# PIC_16F877A_Board_V4.net
KiCad netlist of a schematic drawn in EAGLE
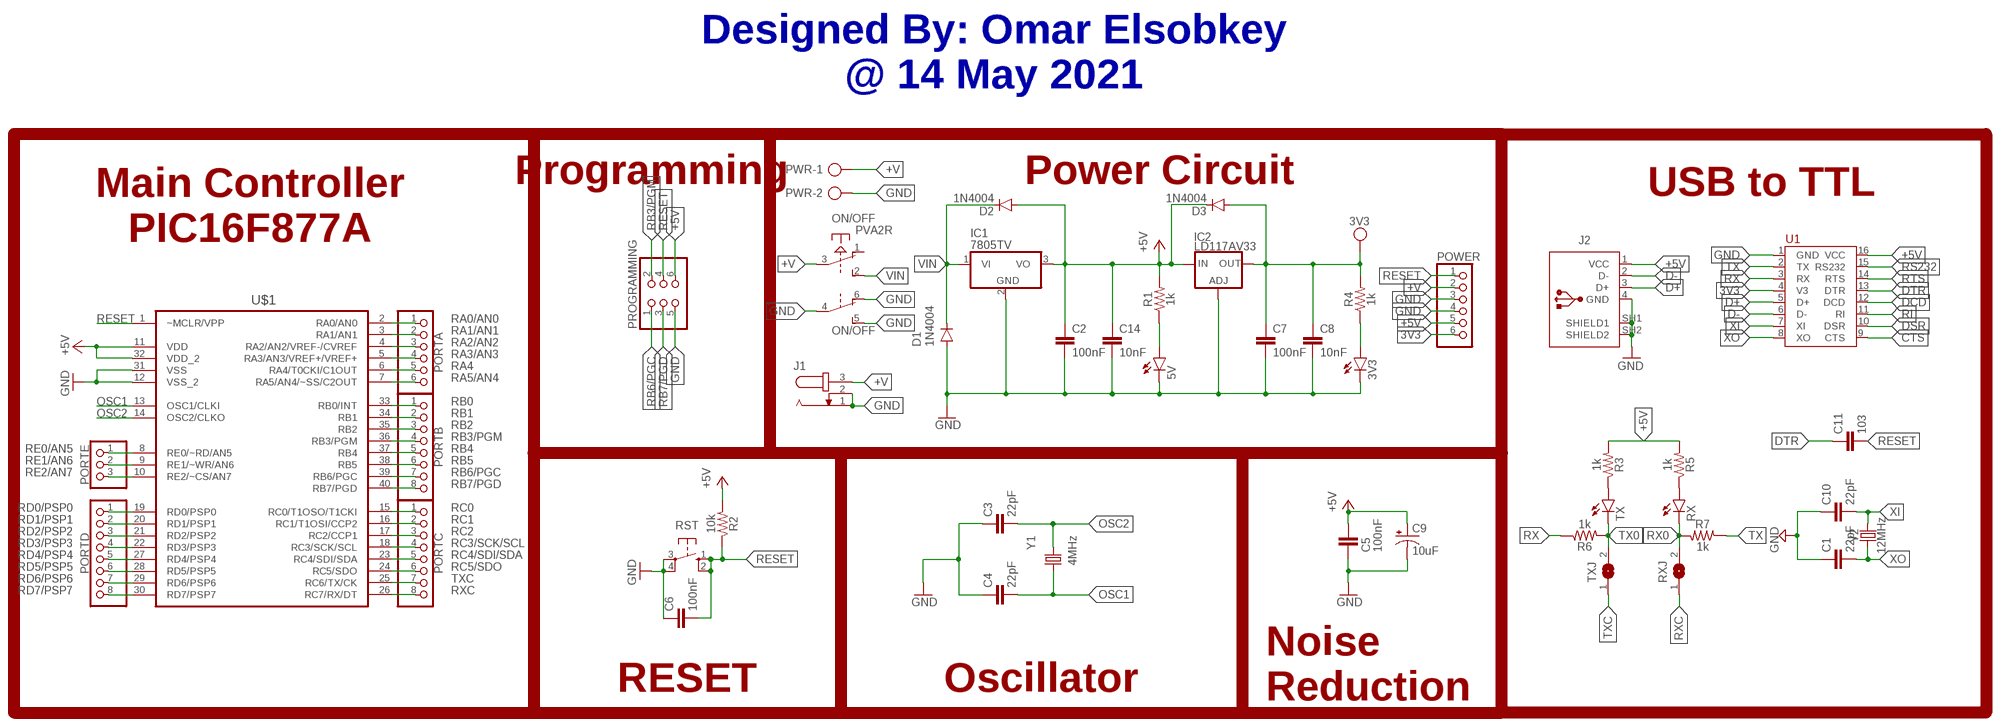
[diagram p0: schematic, sheet 1]

(export (version "E")
  (design (tool "Eeschema 10.0.6"))
  (components
    (comp (ref "3V3")
      (value "LED3MM")
      (footprint "eagle-import:LED3MM")
      (libsource (lib "eagle-import") (part "LED3MM"))
    )
    (comp (ref "5V")
      (value "LED3MM")
      (footprint "eagle-import:LED3MM")
      (libsource (lib "eagle-import") (part "LED3MM"))
    )
    (comp (ref "C1")
      (value "22pF")
      (footprint "eagle-import:C025-025X050")
      (libsource (lib "eagle-import") (part "C-EU025-025X050"))
    )
    (comp (ref "C2")
      (value "100nF")
      (footprint "eagle-import:C025-025X050")
      (libsource (lib "eagle-import") (part "C-EU025-025X050"))
    )
    (comp (ref "C3")
      (value "22pF")
      (footprint "eagle-import:C025-025X050")
      (libsource (lib "eagle-import") (part "C-EU025-025X050"))
    )
    (comp (ref "C4")
      (value "22pF")
      (footprint "eagle-import:C025-025X050")
      (libsource (lib "eagle-import") (part "C-EU025-025X050"))
    )
    (comp (ref "C5")
      (value "100nF")
      (footprint "eagle-import:C025-025X050")
      (libsource (lib "eagle-import") (part "C-EU025-025X050"))
    )
    (comp (ref "C6")
      (value "100nF")
      (footprint "eagle-import:C025-025X050")
      (libsource (lib "eagle-import") (part "C-EU025-025X050"))
    )
    (comp (ref "C7")
      (value "100nF")
      (footprint "eagle-import:C025-025X050")
      (libsource (lib "eagle-import") (part "C-EU025-025X050"))
    )
    (comp (ref "C8")
      (value "10nF")
      (footprint "eagle-import:C025-025X050")
      (libsource (lib "eagle-import") (part "C-EU025-025X050"))
    )
    (comp (ref "C9")
      (value "10uF")
      (footprint "eagle-import:CPOL-RADIAL-2.5MM-5MM-KIT")
      (libsource (lib "eagle-import") (part "10UF-POLAR-RADIAL-2.5MM-KIT-25V-20%"))
    )
    (comp (ref "C10")
      (value "22pF")
      (footprint "eagle-import:C025-025X050")
      (libsource (lib "eagle-import") (part "C-EU025-025X050"))
    )
    (comp (ref "C11")
      (value "103")
      (footprint "eagle-import:C025-025X050")
      (libsource (lib "eagle-import") (part "C-EU025-025X050"))
    )
    (comp (ref "C14")
      (value "10nF")
      (footprint "eagle-import:C025-025X050")
      (libsource (lib "eagle-import") (part "C-EU025-025X050"))
    )
    (comp (ref "D1")
      (value "1N4004")
      (footprint "eagle-import:DO41-10")
      (libsource (lib "eagle-import") (part "1N4004"))
    )
    (comp (ref "D2")
      (value "1N4004")
      (footprint "eagle-import:DO41-10")
      (libsource (lib "eagle-import") (part "1N4004"))
    )
    (comp (ref "D3")
      (value "1N4004")
      (footprint "eagle-import:DO41-10")
      (libsource (lib "eagle-import") (part "1N4004"))
    )
    (comp (ref "IC1")
      (value "7805TV")
      (footprint "eagle-import:TO220V")
      (libsource (lib "eagle-import") (part "78TV05"))
    )
    (comp (ref "IC2")
      (value "LD117AV33")
      (footprint "eagle-import:TO220L1")
      (libsource (lib "eagle-import") (part "LD117A?V33"))
    )
    (comp (ref "J1")
      (value "JACK-PLUG0")
      (footprint "eagle-import:SPC4077")
      (libsource (lib "eagle-import") (part "JACK-PLUG0"))
    )
    (comp (ref "J2")
      (value "61729-1011")
      (footprint "eagle-import:61729-1011BLF")
      (fields (field (name "MANUFACTURER") "Amphenol ICC (FCI)") (field (name "MPN") "61729-1011BLF"))
      (libsource (lib "eagle-import") (part "61729-1011"))
    )
    (comp (ref "ON/OFF")
      (value "PVA2R")
      (footprint "eagle-import:PVA2R")
      (libsource (lib "eagle-import") (part "PVA2R"))
    )
    (comp (ref "PORTA")
      (value "PINHD-1X6")
      (footprint "eagle-import:1X06")
      (libsource (lib "eagle-import") (part "PINHD-1X6"))
    )
    (comp (ref "PORTB")
      (value "PINHD-1X8")
      (footprint "eagle-import:1X08")
      (libsource (lib "eagle-import") (part "PINHD-1X8"))
    )
    (comp (ref "PORTC")
      (value "PINHD-1X8")
      (footprint "eagle-import:1X08")
      (libsource (lib "eagle-import") (part "PINHD-1X8"))
    )
    (comp (ref "PORTD")
      (value "PINHD-1X8")
      (footprint "eagle-import:1X08")
      (libsource (lib "eagle-import") (part "PINHD-1X8"))
    )
    (comp (ref "PORTE")
      (value "PINHD-1X3")
      (footprint "eagle-import:1X03")
      (libsource (lib "eagle-import") (part "PINHD-1X3"))
    )
    (comp (ref "POWER")
      (value "PINHD-1X6")
      (footprint "eagle-import:1X06")
      (libsource (lib "eagle-import") (part "PINHD-1X6"))
    )
    (comp (ref "PROGRAMMING")
      (value "PINHD-2X3")
      (footprint "eagle-import:2X03")
      (libsource (lib "eagle-import") (part "PINHD-2X3"))
    )
    (comp (ref "PWR")
      (value "AK500/2-H")
      (footprint "eagle-import:AK500_2-H")
      (libsource (lib "eagle-import") (part "AK500/2-H"))
    )
    (comp (ref "R1")
      (value "1k")
      (footprint "eagle-import:1206")
      (libsource (lib "eagle-import") (part "RESISTOR1206"))
    )
    (comp (ref "R2")
      (value "10k")
      (footprint "eagle-import:1206")
      (libsource (lib "eagle-import") (part "RESISTOR1206"))
    )
    (comp (ref "R3")
      (value "1k")
      (footprint "eagle-import:1206")
      (libsource (lib "eagle-import") (part "RESISTOR1206"))
    )
    (comp (ref "R4")
      (value "1k")
      (footprint "eagle-import:1206")
      (libsource (lib "eagle-import") (part "RESISTOR1206"))
    )
    (comp (ref "R5")
      (value "1k")
      (footprint "eagle-import:1206")
      (libsource (lib "eagle-import") (part "RESISTOR1206"))
    )
    (comp (ref "R6")
      (value "1k")
      (footprint "eagle-import:1206")
      (libsource (lib "eagle-import") (part "RESISTOR1206"))
    )
    (comp (ref "R7")
      (value "1k")
      (footprint "eagle-import:1206")
      (libsource (lib "eagle-import") (part "RESISTOR1206"))
    )
    (comp (ref "RST")
      (value "10-XX")
      (footprint "eagle-import:B3F-10XX")
      (fields (field (name "MPN") "B3F-1000"))
      (libsource (lib "eagle-import") (part "10-XX"))
    )
    (comp (ref "RX")
      (value "LED3MM")
      (footprint "eagle-import:LED3MM")
      (libsource (lib "eagle-import") (part "LED3MM"))
    )
    (comp (ref "RXJ")
      (value "SJW")
      (footprint "eagle-import:SJW")
      (libsource (lib "eagle-import") (part "SJW"))
    )
    (comp (ref "TX")
      (value "LED3MM")
      (footprint "eagle-import:LED3MM")
      (libsource (lib "eagle-import") (part "LED3MM"))
    )
    (comp (ref "TXJ")
      (value "SJW")
      (footprint "eagle-import:SJW")
      (libsource (lib "eagle-import") (part "SJW"))
    )
    (comp (ref "U$1")
      (value "PIC16F877A-I/P")
      (footprint "eagle-import:PDIP-40")
      (fields (field (name "MF") "Microchip"))
      (libsource (lib "eagle-import") (part "PIC16F877A-I/P"))
    )
    (comp (ref "U1")
      (value "CH340G")
      (footprint "eagle-import:SOP-16")
      (libsource (lib "eagle-import") (part "CH340G"))
    )
    (comp (ref "Y1")
      (value "4MHz")
      (footprint "eagle-import:HC49U")
      (libsource (lib "eagle-import") (part "CRYSTALPTH-HC49UV"))
    )
    (comp (ref "Y2")
      (value "12MHz")
      (footprint "eagle-import:HC49U")
      (libsource (lib "eagle-import") (part "CRYSTALPTH-HC49UV"))
    )
  )
  (nets
    (net (code "1") (name "+5V") (class "Default")
      (node (ref "C14") (pin "1") (pinfunction "1_1") (pintype "passive"))
      (node (ref "C2") (pin "1") (pinfunction "1_1") (pintype "passive"))
      (node (ref "C5") (pin "2") (pinfunction "2_2") (pintype "passive"))
      (node (ref "C9") (pin "1") (pinfunction "+_1") (pintype "passive"))
      (node (ref "D2") (pin "A") (pinfunction "A_A") (pintype "passive"))
      (node (ref "D3") (pin "C") (pinfunction "C_C") (pintype "passive"))
      (node (ref "IC1") (pin "3") (pinfunction "VO_3") (pintype "passive"))
      (node (ref "IC2") (pin "3") (pinfunction "IN_3") (pintype "input"))
      (node (ref "J2") (pin "1") (pinfunction "VCC_1") (pintype "power_in"))
      (node (ref "POWER") (pin "5") (pinfunction "5_5") (pintype "passive"))
      (node (ref "PROGRAMMING") (pin "6") (pinfunction "6_6") (pintype "passive"))
      (node (ref "R1") (pin "2") (pinfunction "2_2") (pintype "passive"))
      (node (ref "R2") (pin "2") (pinfunction "2_2") (pintype "passive"))
      (node (ref "R3") (pin "2") (pinfunction "2_2") (pintype "passive"))
      (node (ref "R5") (pin "2") (pinfunction "2_2") (pintype "passive"))
      (node (ref "U$1") (pin "11") (pinfunction "VDD_11") (pintype "power_in"))
      (node (ref "U$1") (pin "32") (pinfunction "VDD_2_32") (pintype "power_in"))
      (node (ref "U1") (pin "16") (pinfunction "VCC_16") (pintype "bidirectional"))
    )
    (net (code "2") (name "+V") (class "Default")
      (node (ref "J1") (pin "3") (pinfunction "3_3") (pintype "passive"))
      (node (ref "ON/OFF") (pin "3") (pinfunction "P_3") (pintype "passive"))
      (node (ref "POWER") (pin "2") (pinfunction "2_2") (pintype "passive"))
      (node (ref "PWR") (pin "1") (pinfunction "KL_1") (pintype "passive"))
    )
    (net (code "3") (name "/RA0{slash}AN0") (class "Default")
      (node (ref "PORTA") (pin "1") (pinfunction "1_1") (pintype "passive"))
      (node (ref "U$1") (pin "2") (pinfunction "RA0/AN0_2") (pintype "bidirectional"))
    )
    (net (code "4") (name "/RA1{slash}AN1") (class "Default")
      (node (ref "PORTA") (pin "2") (pinfunction "2_2") (pintype "passive"))
      (node (ref "U$1") (pin "3") (pinfunction "RA1/AN1_3") (pintype "bidirectional"))
    )
    (net (code "5") (name "/RA2{slash}AN2") (class "Default")
      (node (ref "PORTA") (pin "3") (pinfunction "3_3") (pintype "passive"))
      (node (ref "U$1") (pin "4") (pinfunction "RA2/AN2/VREF-/CVREF_4") (pintype "bidirectional"))
    )
    (net (code "6") (name "/RA3{slash}AN3") (class "Default")
      (node (ref "PORTA") (pin "4") (pinfunction "4_4") (pintype "passive"))
      (node (ref "U$1") (pin "5") (pinfunction "RA3/AN3/VREF+/VREF+_5") (pintype "bidirectional"))
    )
    (net (code "7") (name "/RA4") (class "Default")
      (node (ref "PORTA") (pin "5") (pinfunction "5_5") (pintype "passive"))
      (node (ref "U$1") (pin "6") (pinfunction "RA4/T0CKI/C1OUT_6") (pintype "bidirectional"))
    )
    (net (code "8") (name "/RA5{slash}AN4") (class "Default")
      (node (ref "PORTA") (pin "6") (pinfunction "6_6") (pintype "passive"))
      (node (ref "U$1") (pin "7") (pinfunction "RA5/AN4/~{SS/C2OUT}_7") (pintype "bidirectional"))
    )
    (net (code "9") (name "/RB0") (class "Default")
      (node (ref "PORTB") (pin "1") (pinfunction "1_1") (pintype "passive"))
      (node (ref "U$1") (pin "33") (pinfunction "RB0/INT_33") (pintype "bidirectional"))
    )
    (net (code "10") (name "/RB1") (class "Default")
      (node (ref "PORTB") (pin "2") (pinfunction "2_2") (pintype "passive"))
      (node (ref "U$1") (pin "34") (pinfunction "RB1_34") (pintype "bidirectional"))
    )
    (net (code "11") (name "/RB2") (class "Default")
      (node (ref "PORTB") (pin "3") (pinfunction "3_3") (pintype "passive"))
      (node (ref "U$1") (pin "35") (pinfunction "RB2_35") (pintype "bidirectional"))
    )
    (net (code "12") (name "/RB4") (class "Default")
      (node (ref "PORTB") (pin "5") (pinfunction "5_5") (pintype "passive"))
      (node (ref "U$1") (pin "37") (pinfunction "RB4_37") (pintype "bidirectional"))
    )
    (net (code "13") (name "/RB5") (class "Default")
      (node (ref "PORTB") (pin "6") (pinfunction "6_6") (pintype "passive"))
      (node (ref "U$1") (pin "38") (pinfunction "RB5_38") (pintype "bidirectional"))
    )
    (net (code "14") (name "/RC0") (class "Default")
      (node (ref "PORTC") (pin "1") (pinfunction "1_1") (pintype "passive"))
      (node (ref "U$1") (pin "15") (pinfunction "RC0/T1OSO/T1CKI_15") (pintype "bidirectional"))
    )
    (net (code "15") (name "/RC1") (class "Default")
      (node (ref "PORTC") (pin "2") (pinfunction "2_2") (pintype "passive"))
      (node (ref "U$1") (pin "16") (pinfunction "RC1/T1OSI/CCP2_16") (pintype "bidirectional"))
    )
    (net (code "16") (name "/RC2") (class "Default")
      (node (ref "PORTC") (pin "3") (pinfunction "3_3") (pintype "passive"))
      (node (ref "U$1") (pin "17") (pinfunction "RC2/CCP1_17") (pintype "bidirectional"))
    )
    (net (code "17") (name "/RC3{slash}SCK{slash}SCL") (class "Default")
      (node (ref "PORTC") (pin "4") (pinfunction "4_4") (pintype "passive"))
      (node (ref "U$1") (pin "18") (pinfunction "RC3/SCK/SCL_18") (pintype "bidirectional"))
    )
    (net (code "18") (name "/RC4{slash}SDI{slash}SDA") (class "Default")
      (node (ref "PORTC") (pin "5") (pinfunction "5_5") (pintype "passive"))
      (node (ref "U$1") (pin "23") (pinfunction "RC4/SDI/SDA_23") (pintype "bidirectional"))
    )
    (net (code "19") (name "/RC5{slash}SDO") (class "Default")
      (node (ref "PORTC") (pin "6") (pinfunction "6_6") (pintype "passive"))
      (node (ref "U$1") (pin "24") (pinfunction "RC5/SDO_24") (pintype "bidirectional"))
    )
    (net (code "20") (name "/RD0{slash}PSP0") (class "Default")
      (node (ref "PORTD") (pin "1") (pinfunction "1_1") (pintype "passive"))
      (node (ref "U$1") (pin "19") (pinfunction "RD0/PSP0_19") (pintype "bidirectional"))
    )
    (net (code "21") (name "/RD1{slash}PSP1") (class "Default")
      (node (ref "PORTD") (pin "2") (pinfunction "2_2") (pintype "passive"))
      (node (ref "U$1") (pin "20") (pinfunction "RD1/PSP1_20") (pintype "bidirectional"))
    )
    (net (code "22") (name "/RD2{slash}PSP2") (class "Default")
      (node (ref "PORTD") (pin "3") (pinfunction "3_3") (pintype "passive"))
      (node (ref "U$1") (pin "21") (pinfunction "RD2/PSP2_21") (pintype "bidirectional"))
    )
    (net (code "23") (name "/RD3{slash}PSP3") (class "Default")
      (node (ref "PORTD") (pin "4") (pinfunction "4_4") (pintype "passive"))
      (node (ref "U$1") (pin "22") (pinfunction "RD3/PSP3_22") (pintype "bidirectional"))
    )
    (net (code "24") (name "/RD4{slash}PSP4") (class "Default")
      (node (ref "PORTD") (pin "5") (pinfunction "5_5") (pintype "passive"))
      (node (ref "U$1") (pin "27") (pinfunction "RD4/PSP4_27") (pintype "bidirectional"))
    )
    (net (code "25") (name "/RD5{slash}PSP5") (class "Default")
      (node (ref "PORTD") (pin "6") (pinfunction "6_6") (pintype "passive"))
      (node (ref "U$1") (pin "28") (pinfunction "RD5/PSP5_28") (pintype "bidirectional"))
    )
    (net (code "26") (name "/RD6{slash}PSP6") (class "Default")
      (node (ref "PORTD") (pin "7") (pinfunction "7_7") (pintype "passive"))
      (node (ref "U$1") (pin "29") (pinfunction "RD6/PSP6_29") (pintype "bidirectional"))
    )
    (net (code "27") (name "/RD7{slash}PSP7") (class "Default")
      (node (ref "PORTD") (pin "8") (pinfunction "8_8") (pintype "passive"))
      (node (ref "U$1") (pin "30") (pinfunction "RD7/PSP7_30") (pintype "bidirectional"))
    )
    (net (code "28") (name "/RE0{slash}AN5") (class "Default")
      (node (ref "PORTE") (pin "1") (pinfunction "1_1") (pintype "passive"))
      (node (ref "U$1") (pin "8") (pinfunction "RE0/~{RD/AN5}_8") (pintype "bidirectional"))
    )
    (net (code "29") (name "/RE1{slash}AN6") (class "Default")
      (node (ref "PORTE") (pin "2") (pinfunction "2_2") (pintype "passive"))
      (node (ref "U$1") (pin "9") (pinfunction "RE1/~{WR/AN6}_9") (pintype "bidirectional"))
    )
    (net (code "30") (name "/RE2{slash}AN7") (class "Default")
      (node (ref "PORTE") (pin "3") (pinfunction "3_3") (pintype "passive"))
      (node (ref "U$1") (pin "10") (pinfunction "RE2/~{CS/AN7}_10") (pintype "bidirectional"))
    )
    (net (code "31") (name "3V3") (class "Default")
      (node (ref "C7") (pin "1") (pinfunction "1_1") (pintype "passive"))
      (node (ref "C8") (pin "1") (pinfunction "1_1") (pintype "passive"))
      (node (ref "D3") (pin "A") (pinfunction "A_A") (pintype "passive"))
      (node (ref "IC2") (pin "2") (pinfunction "OUT_2") (pintype "passive"))
      (node (ref "POWER") (pin "6") (pinfunction "6_6") (pintype "passive"))
      (node (ref "R4") (pin "2") (pinfunction "2_2") (pintype "passive"))
      (node (ref "U1") (pin "4") (pinfunction "V3_4") (pintype "bidirectional"))
    )
    (net (code "32") (name "CTS") (class "Default")
      (node (ref "U1") (pin "9") (pinfunction "CTS_9") (pintype "bidirectional"))
    )
    (net (code "33") (name "D+") (class "Default")
      (node (ref "J2") (pin "3") (pinfunction "D+_3") (pintype "bidirectional"))
      (node (ref "U1") (pin "5") (pinfunction "D+_5") (pintype "bidirectional"))
    )
    (net (code "34") (name "D-") (class "Default")
      (node (ref "J2") (pin "2") (pinfunction "D-_2") (pintype "bidirectional"))
      (node (ref "U1") (pin "6") (pinfunction "D-_6") (pintype "bidirectional"))
    )
    (net (code "35") (name "DCD") (class "Default")
      (node (ref "U1") (pin "12") (pinfunction "DCD_12") (pintype "bidirectional"))
    )
    (net (code "36") (name "DSR") (class "Default")
      (node (ref "U1") (pin "10") (pinfunction "DSR_10") (pintype "bidirectional"))
    )
    (net (code "37") (name "DTR") (class "Default")
      (node (ref "C11") (pin "1") (pinfunction "1_1") (pintype "passive"))
      (node (ref "U1") (pin "13") (pinfunction "DTR_13") (pintype "bidirectional"))
    )
    (net (code "38") (name "GND") (class "Default")
      (node (ref "3V3") (pin "K") (pinfunction "C_K") (pintype "passive"))
      (node (ref "5V") (pin "K") (pinfunction "C_K") (pintype "passive"))
      (node (ref "C1") (pin "1") (pinfunction "1_1") (pintype "passive"))
      (node (ref "C10") (pin "1") (pinfunction "1_1") (pintype "passive"))
      (node (ref "C14") (pin "2") (pinfunction "2_2") (pintype "passive"))
      (node (ref "C2") (pin "2") (pinfunction "2_2") (pintype "passive"))
      (node (ref "C3") (pin "1") (pinfunction "1_1") (pintype "passive"))
      (node (ref "C4") (pin "1") (pinfunction "1_1") (pintype "passive"))
      (node (ref "C5") (pin "1") (pinfunction "1_1") (pintype "passive"))
      (node (ref "C6") (pin "1") (pinfunction "1_1") (pintype "passive"))
      (node (ref "C7") (pin "2") (pinfunction "2_2") (pintype "passive"))
      (node (ref "C8") (pin "2") (pinfunction "2_2") (pintype "passive"))
      (node (ref "C9") (pin "2") (pinfunction "-_2") (pintype "passive"))
      (node (ref "D1") (pin "A") (pinfunction "A_A") (pintype "passive"))
      (node (ref "IC1") (pin "2") (pinfunction "GND_2") (pintype "passive"))
      (node (ref "IC2") (pin "1") (pinfunction "ADJ_1") (pintype "input"))
      (node (ref "J1") (pin "1") (pinfunction "1_1") (pintype "passive"))
      (node (ref "J1") (pin "2") (pinfunction "2_2") (pintype "passive"))
      (node (ref "J2") (pin "4") (pinfunction "GND_4") (pintype "power_in"))
      (node (ref "J2") (pin "SH1") (pinfunction "SHIELD1_SH1") (pintype "power_in"))
      (node (ref "J2") (pin "SH2") (pinfunction "SHIELD2_SH2") (pintype "power_in"))
      (node (ref "ON/OFF") (pin "4") (pinfunction "P_4") (pintype "passive"))
      (node (ref "ON/OFF") (pin "5") (pinfunction "S_5") (pintype "passive"))
      (node (ref "ON/OFF") (pin "6") (pinfunction "O_6") (pintype "passive"))
      (node (ref "POWER") (pin "3") (pinfunction "3_3") (pintype "passive"))
      (node (ref "POWER") (pin "4") (pinfunction "4_4") (pintype "passive"))
      (node (ref "PROGRAMMING") (pin "5") (pinfunction "5_5") (pintype "passive"))
      (node (ref "PWR") (pin "2") (pinfunction "KL_2") (pintype "passive"))
      (node (ref "RST") (pin "3") (pinfunction "P_3") (pintype "passive"))
      (node (ref "RST") (pin "4") (pinfunction "P1_4") (pintype "passive"))
      (node (ref "U$1") (pin "12") (pinfunction "VSS_2_12") (pintype "power_in"))
      (node (ref "U$1") (pin "31") (pinfunction "VSS_31") (pintype "power_in"))
      (node (ref "U1") (pin "1") (pinfunction "GND_1") (pintype "bidirectional"))
    )
    (net (code "39") (name "Net-(3V3-PadA)") (class "Default")
      (node (ref "3V3") (pin "A") (pinfunction "A_A") (pintype "passive"))
      (node (ref "R4") (pin "1") (pinfunction "1_1") (pintype "passive"))
    )
    (net (code "40") (name "Net-(5V-PadA)") (class "Default")
      (node (ref "5V") (pin "A") (pinfunction "A_A") (pintype "passive"))
      (node (ref "R1") (pin "1") (pinfunction "1_1") (pintype "passive"))
    )
    (net (code "41") (name "Net-(R3-Pad1)") (class "Default")
      (node (ref "R3") (pin "1") (pinfunction "1_1") (pintype "passive"))
      (node (ref "TX") (pin "A") (pinfunction "A_A") (pintype "passive"))
    )
    (net (code "42") (name "Net-(R5-Pad1)") (class "Default")
      (node (ref "R5") (pin "1") (pinfunction "1_1") (pintype "passive"))
      (node (ref "RX") (pin "A") (pinfunction "A_A") (pintype "passive"))
    )
    (net (code "43") (name "OSC1") (class "Default")
      (node (ref "C4") (pin "2") (pinfunction "2_2") (pintype "passive"))
      (node (ref "U$1") (pin "13") (pinfunction "OSC1/CLKI_13") (pintype "input"))
      (node (ref "Y1") (pin "2") (pinfunction "2_2") (pintype "passive"))
    )
    (net (code "44") (name "OSC2") (class "Default")
      (node (ref "C3") (pin "2") (pinfunction "2_2") (pintype "passive"))
      (node (ref "U$1") (pin "14") (pinfunction "OSC2/CLKO_14") (pintype "output"))
      (node (ref "Y1") (pin "1") (pinfunction "1_1") (pintype "passive"))
    )
    (net (code "45") (name "RB3{slash}PGM") (class "Default")
      (node (ref "PORTB") (pin "4") (pinfunction "4_4") (pintype "passive"))
      (node (ref "PROGRAMMING") (pin "2") (pinfunction "2_2") (pintype "passive"))
      (node (ref "U$1") (pin "36") (pinfunction "RB3/PGM_36") (pintype "bidirectional"))
    )
    (net (code "46") (name "RB6{slash}PGC") (class "Default")
      (node (ref "PORTB") (pin "7") (pinfunction "7_7") (pintype "passive"))
      (node (ref "PROGRAMMING") (pin "1") (pinfunction "1_1") (pintype "passive"))
      (node (ref "U$1") (pin "39") (pinfunction "RB6/PGC_39") (pintype "bidirectional"))
    )
    (net (code "47") (name "RB7{slash}PGD") (class "Default")
      (node (ref "PORTB") (pin "8") (pinfunction "8_8") (pintype "passive"))
      (node (ref "PROGRAMMING") (pin "3") (pinfunction "3_3") (pintype "passive"))
      (node (ref "U$1") (pin "40") (pinfunction "RB7/PGD_40") (pintype "bidirectional"))
    )
    (net (code "48") (name "RESET") (class "Default")
      (node (ref "C11") (pin "2") (pinfunction "2_2") (pintype "passive"))
      (node (ref "C6") (pin "2") (pinfunction "2_2") (pintype "passive"))
      (node (ref "POWER") (pin "1") (pinfunction "1_1") (pintype "passive"))
      (node (ref "PROGRAMMING") (pin "4") (pinfunction "4_4") (pintype "passive"))
      (node (ref "R2") (pin "1") (pinfunction "1_1") (pintype "passive"))
      (node (ref "RST") (pin "1") (pinfunction "S_1") (pintype "passive"))
      (node (ref "RST") (pin "2") (pinfunction "S1_2") (pintype "passive"))
      (node (ref "U$1") (pin "1") (pinfunction "~{MCLR/VPP}_1") (pintype "input"))
    )
    (net (code "49") (name "RI") (class "Default")
      (node (ref "U1") (pin "11") (pinfunction "RI_11") (pintype "bidirectional"))
    )
    (net (code "50") (name "RS232") (class "Default")
      (node (ref "U1") (pin "15") (pinfunction "RS232_15") (pintype "bidirectional"))
    )
    (net (code "51") (name "RTS") (class "Default")
      (node (ref "U1") (pin "14") (pinfunction "RTS_14") (pintype "bidirectional"))
    )
    (net (code "52") (name "RX") (class "Default")
      (node (ref "R6") (pin "1") (pinfunction "1_1") (pintype "passive"))
      (node (ref "U1") (pin "3") (pinfunction "RX_3") (pintype "bidirectional"))
    )
    (net (code "53") (name "RX0") (class "Default")
      (node (ref "R7") (pin "2") (pinfunction "2_2") (pintype "passive"))
      (node (ref "RX") (pin "K") (pinfunction "C_K") (pintype "passive"))
      (node (ref "RXJ") (pin "2") (pinfunction "2_2") (pintype "passive"))
    )
    (net (code "54") (name "RXC") (class "Default")
      (node (ref "PORTC") (pin "8") (pinfunction "8_8") (pintype "passive"))
      (node (ref "RXJ") (pin "1") (pinfunction "1_1") (pintype "passive"))
      (node (ref "U$1") (pin "26") (pinfunction "RC7/RX/DT_26") (pintype "bidirectional"))
    )
    (net (code "55") (name "TX") (class "Default")
      (node (ref "R7") (pin "1") (pinfunction "1_1") (pintype "passive"))
      (node (ref "U1") (pin "2") (pinfunction "TX_2") (pintype "bidirectional"))
    )
    (net (code "56") (name "TX0") (class "Default")
      (node (ref "R6") (pin "2") (pinfunction "2_2") (pintype "passive"))
      (node (ref "TX") (pin "K") (pinfunction "C_K") (pintype "passive"))
      (node (ref "TXJ") (pin "2") (pinfunction "2_2") (pintype "passive"))
    )
    (net (code "57") (name "TXC") (class "Default")
      (node (ref "PORTC") (pin "7") (pinfunction "7_7") (pintype "passive"))
      (node (ref "TXJ") (pin "1") (pinfunction "1_1") (pintype "passive"))
      (node (ref "U$1") (pin "25") (pinfunction "RC6/TX/CK_25") (pintype "bidirectional"))
    )
    (net (code "58") (name "VIN") (class "Default")
      (node (ref "D1") (pin "C") (pinfunction "C_C") (pintype "passive"))
      (node (ref "D2") (pin "C") (pinfunction "C_C") (pintype "passive"))
      (node (ref "IC1") (pin "1") (pinfunction "VI_1") (pintype "input"))
      (node (ref "ON/OFF") (pin "2") (pinfunction "S_2") (pintype "passive"))
    )
    (net (code "59") (name "XI") (class "Default")
      (node (ref "C10") (pin "2") (pinfunction "2_2") (pintype "passive"))
      (node (ref "U1") (pin "7") (pinfunction "XI_7") (pintype "bidirectional"))
      (node (ref "Y2") (pin "2") (pinfunction "2_2") (pintype "passive"))
    )
    (net (code "60") (name "XO") (class "Default")
      (node (ref "C1") (pin "2") (pinfunction "2_2") (pintype "passive"))
      (node (ref "U1") (pin "8") (pinfunction "XO_8") (pintype "bidirectional"))
      (node (ref "Y2") (pin "1") (pinfunction "1_1") (pintype "passive"))
    )
    (net (code "61") (name "unconnected-(ON/OFFA-O-Pad1)") (class "Default")
      (node (ref "ON/OFF") (pin "1") (pinfunction "O_1") (pintype "passive"))
    )
  )
)
